# ICS40300-Silicon-Mic_Rev-D.net
KiCad netlist of a schematic drawn in EAGLE
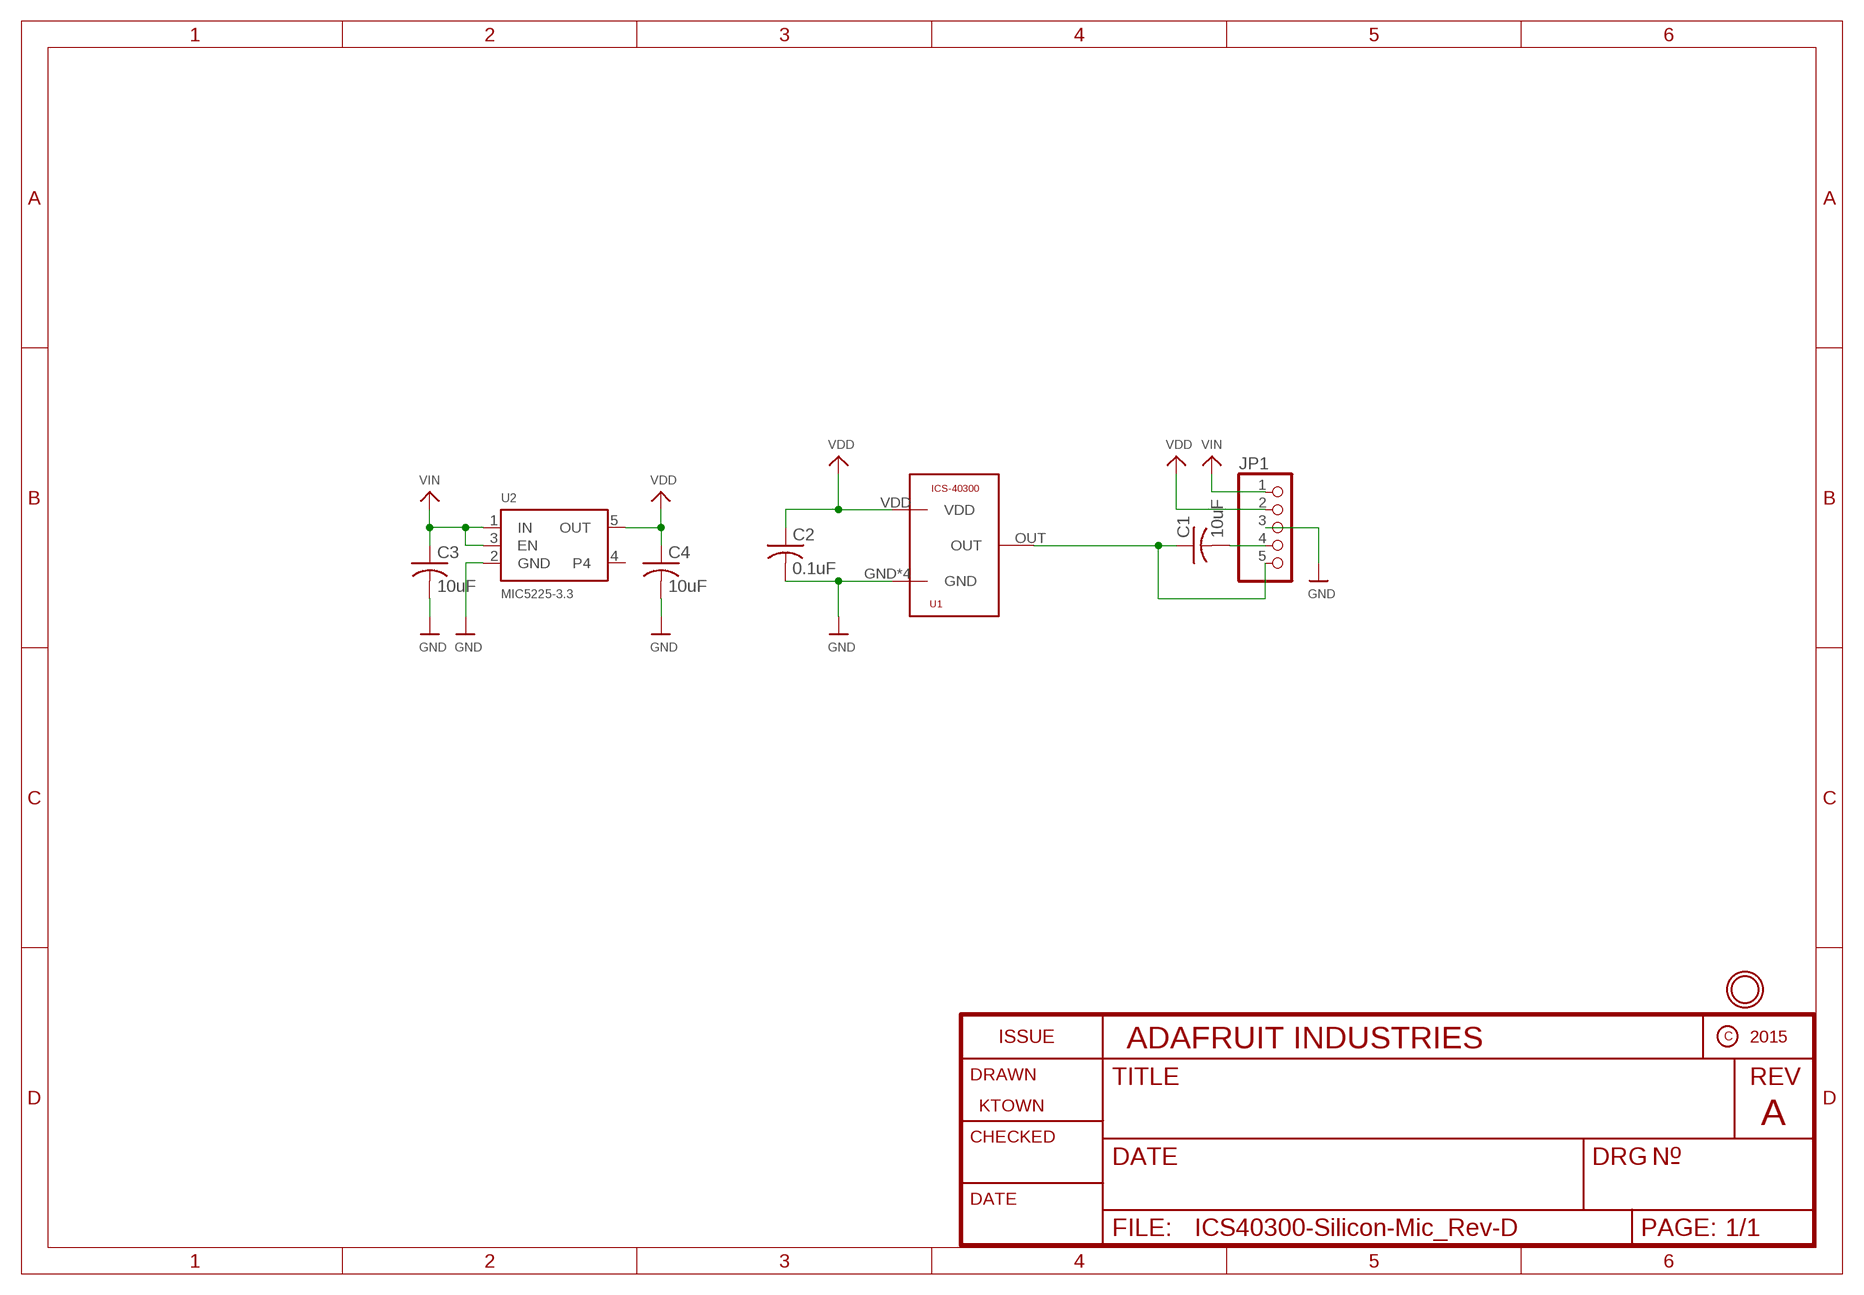
[diagram p0: schematic, sheet 1]

(export (version "E")
  (design (tool "Eeschema 10.0.6"))
  (components
    (comp (ref "C1")
      (value "10uF")
      (footprint "eagle-import:C0805K")
      (libsource (lib "eagle-import") (part "C-USC0805K"))
    )
    (comp (ref "C2")
      (value "0.1uF")
      (footprint "eagle-import:C0805K")
      (libsource (lib "eagle-import") (part "C-USC0805K"))
    )
    (comp (ref "C3")
      (value "10uF")
      (footprint "eagle-import:C0805K")
      (libsource (lib "eagle-import") (part "C-USC0805K"))
    )
    (comp (ref "C4")
      (value "10uF")
      (footprint "eagle-import:C0805K")
      (libsource (lib "eagle-import") (part "C-USC0805K"))
    )
    (comp (ref "JP1")
      (value "HEADER-1X576MIL")
      (footprint "eagle-import:1X05_ROUND_76")
      (libsource (lib "eagle-import") (part "HEADER-1X576MIL"))
    )
    (comp (ref "U$12")
      (value "MOUNTINGHOLE2.5")
      (footprint "eagle-import:MOUNTINGHOLE_2.5_PLATED")
      (libsource (lib "eagle-import") (part "MOUNTINGHOLE2.5"))
    )
    (comp (ref "U1")
      (value "ICS-40300")
      (footprint "eagle-import:ICS-40300")
      (libsource (lib "eagle-import") (part "ICS-40300"))
    )
    (comp (ref "U2")
      (value "MIC5225-3.3")
      (footprint "eagle-import:SOT23-5")
      (libsource (lib "eagle-import") (part "VREG_SOT23-5"))
    )
  )
  (nets
    (net (code "1") (name "GND") (class "Default")
      (node (ref "C2") (pin "2") (pinfunction "2_2") (pintype "passive"))
      (node (ref "C3") (pin "2") (pinfunction "2_2") (pintype "passive"))
      (node (ref "C4") (pin "2") (pinfunction "2_2") (pintype "passive"))
      (node (ref "JP1") (pin "3") (pinfunction "3_3") (pintype "passive"))
      (node (ref "U1") (pin "GND") (pinfunction "GND_GND") (pintype "bidirectional"))
      (node (ref "U1") (pin "GND1") (pinfunction "GND_GND1") (pintype "bidirectional"))
      (node (ref "U1") (pin "GND2") (pinfunction "GND_GND2") (pintype "bidirectional"))
      (node (ref "U1") (pin "GND3") (pinfunction "GND_GND3") (pintype "bidirectional"))
      (node (ref "U2") (pin "2") (pinfunction "GND_2") (pintype "power_in"))
    )
    (net (code "2") (name "Net-(C1-Pad1)") (class "Default")
      (node (ref "C1") (pin "1") (pinfunction "1_1") (pintype "passive"))
      (node (ref "JP1") (pin "5") (pinfunction "5_5") (pintype "passive"))
      (node (ref "U1") (pin "OUT") (pinfunction "OUT_OUT") (pintype "bidirectional"))
    )
    (net (code "3") (name "Net-(C1-Pad2)") (class "Default")
      (node (ref "C1") (pin "2") (pinfunction "2_2") (pintype "passive"))
      (node (ref "JP1") (pin "4") (pinfunction "4_4") (pintype "passive"))
    )
    (net (code "4") (name "VDD") (class "Default")
      (node (ref "C2") (pin "1") (pinfunction "1_1") (pintype "passive"))
      (node (ref "C4") (pin "1") (pinfunction "1_1") (pintype "passive"))
      (node (ref "JP1") (pin "2") (pinfunction "2_2") (pintype "passive"))
      (node (ref "U1") (pin "VDD") (pinfunction "VDD_VDD") (pintype "bidirectional"))
      (node (ref "U2") (pin "5") (pinfunction "OUT_5") (pintype "power_in"))
    )
    (net (code "5") (name "VIN") (class "Default")
      (node (ref "C3") (pin "1") (pinfunction "1_1") (pintype "passive"))
      (node (ref "JP1") (pin "1") (pinfunction "1_1") (pintype "passive"))
      (node (ref "U2") (pin "1") (pinfunction "IN_1") (pintype "power_in"))
      (node (ref "U2") (pin "3") (pinfunction "EN_3") (pintype "input"))
    )
    (net (code "6") (name "unconnected-(U2-P4-Pad4)") (class "Default")
      (node (ref "U2") (pin "4") (pinfunction "P4_4") (pintype "bidirectional"))
    )
  )
)
